# teensy_ms.net
KiCad netlist of a schematic drawn in EAGLE
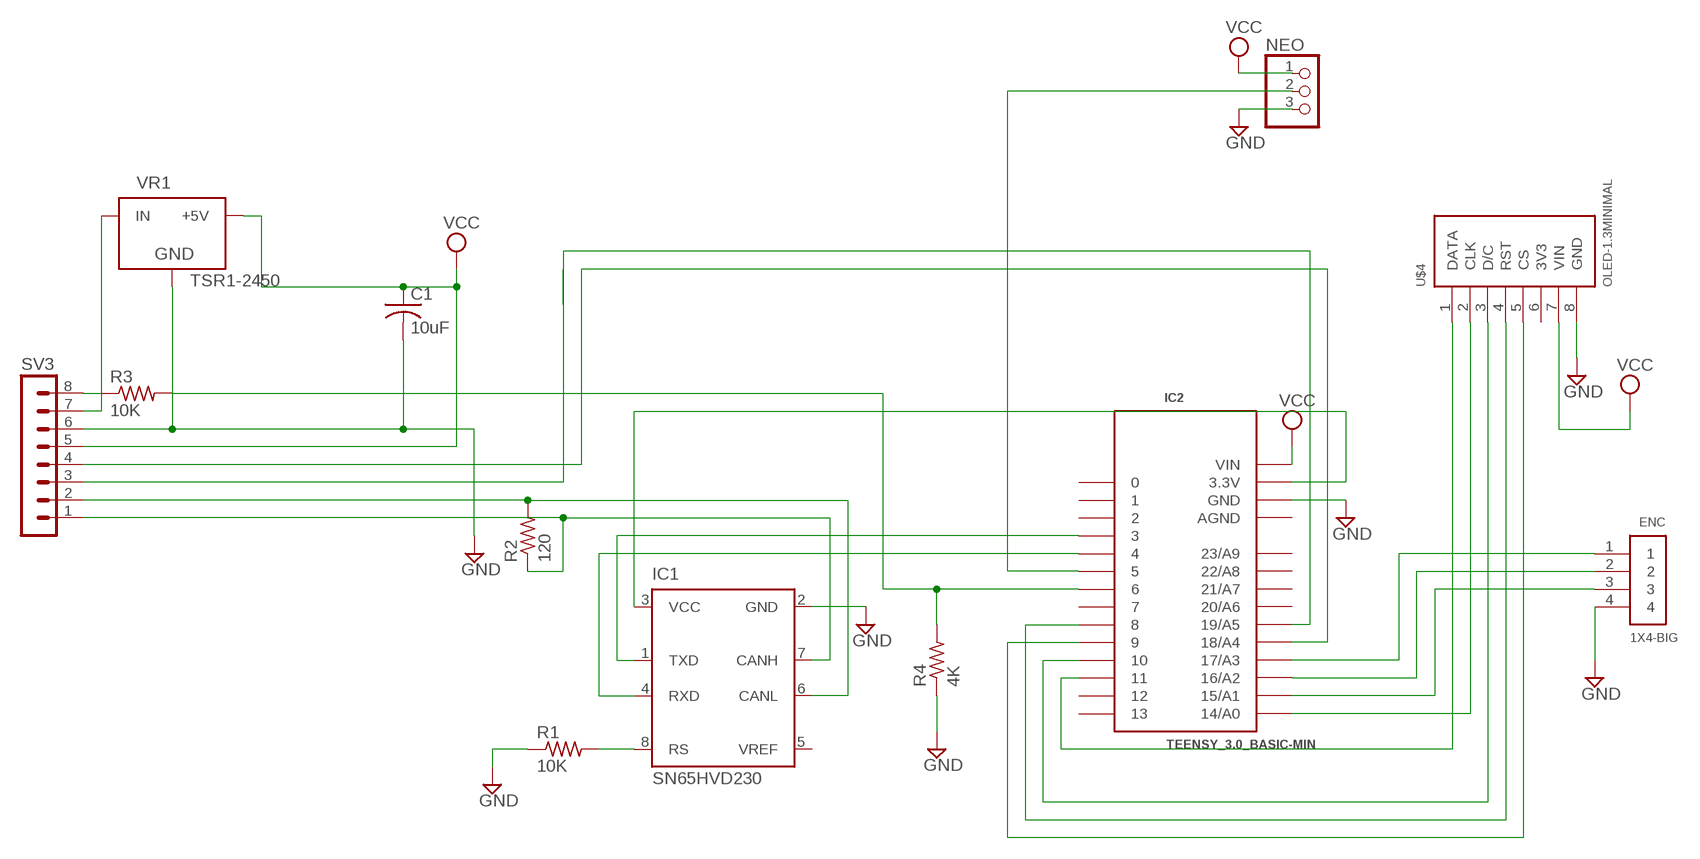
[diagram p0: schematic, sheet 1]

(export (version "E")
  (design (tool "Eeschema 10.0.6"))
  (components
    (comp (ref "C1")
      (value "10uF")
      (footprint "eagle-import:C1206")
      (libsource (lib "eagle-import") (part "C-USC1206"))
    )
    (comp (ref "ENC")
      (value "1X4-BIG")
      (footprint "eagle-import:1X04-BIG")
      (libsource (lib "eagle-import") (part "1X4-BIG"))
    )
    (comp (ref "IC1")
      (value "SN65HVD230")
      (footprint "eagle-import:SO8")
      (libsource (lib "eagle-import") (part "SN65HVD230"))
    )
    (comp (ref "IC2")
      (value "TEENSY_3.0_BASIC-MIN")
      (footprint "eagle-import:TEESNY_3.0_BASIC-MIN")
      (libsource (lib "eagle-import") (part "TEENSY_3.0_BASIC-MIN"))
    )
    (comp (ref "NEO")
      (value "PINHD-1X3")
      (footprint "eagle-import:1X03")
      (libsource (lib "eagle-import") (part "PINHD-1X3"))
    )
    (comp (ref "R1")
      (value "10K")
      (footprint "eagle-import:M1206")
      (libsource (lib "eagle-import") (part "R-US_M1206"))
    )
    (comp (ref "R2")
      (value "120")
      (footprint "eagle-import:M1206")
      (libsource (lib "eagle-import") (part "R-US_M1206"))
    )
    (comp (ref "R3")
      (value "10K")
      (footprint "eagle-import:M1206")
      (libsource (lib "eagle-import") (part "R-US_M1206"))
    )
    (comp (ref "R4")
      (value "4K")
      (footprint "eagle-import:M1206")
      (libsource (lib "eagle-import") (part "R-US_M1206"))
    )
    (comp (ref "SV3")
      (value "MA08-1")
      (footprint "eagle-import:MA08-1")
      (libsource (lib "eagle-import") (part "MA08-1"))
    )
    (comp (ref "U$4")
      (value "OLED-1.3MINIMAL")
      (footprint "eagle-import:OLED-1.3-BARE")
      (libsource (lib "eagle-import") (part "OLED-1.3MINIMAL"))
    )
    (comp (ref "VR1")
      (value "TSR1-2450")
      (footprint "eagle-import:TSR-1")
      (libsource (lib "eagle-import") (part "TSR1-2450"))
    )
  )
  (nets
    (net (code "1") (name "/AGND") (class "Default")
      (node (ref "IC2") (pin "AGND") (pinfunction "AGND_AGND") (pintype "power_in"))
    )
    (net (code "2") (name "GND") (class "Default")
      (node (ref "C1") (pin "2") (pinfunction "2_2") (pintype "passive"))
      (node (ref "ENC") (pin "4") (pinfunction "4_4") (pintype "bidirectional"))
      (node (ref "IC1") (pin "2") (pinfunction "GND_2") (pintype "power_in"))
      (node (ref "IC2") (pin "GND") (pinfunction "GND_GND") (pintype "power_in"))
      (node (ref "NEO") (pin "3") (pinfunction "3_3") (pintype "passive"))
      (node (ref "R1") (pin "1") (pinfunction "1_1") (pintype "passive"))
      (node (ref "R4") (pin "1") (pinfunction "1_1") (pintype "passive"))
      (node (ref "SV3") (pin "6") (pinfunction "6_6") (pintype "passive"))
      (node (ref "U$4") (pin "8") (pinfunction "GND_8") (pintype "bidirectional"))
      (node (ref "VR1") (pin "2") (pinfunction "GND_2") (pintype "power_in"))
    )
    (net (code "3") (name "Net-(ENC-Pad1)") (class "Default")
      (node (ref "ENC") (pin "1") (pinfunction "1_1") (pintype "bidirectional"))
      (node (ref "IC2") (pin "17/A3") (pinfunction "17/A3_17/A3") (pintype "bidirectional"))
    )
    (net (code "4") (name "Net-(ENC-Pad2)") (class "Default")
      (node (ref "ENC") (pin "2") (pinfunction "2_2") (pintype "bidirectional"))
      (node (ref "IC2") (pin "16/A2") (pinfunction "16/A2_16/A2") (pintype "bidirectional"))
    )
    (net (code "5") (name "Net-(ENC-Pad3)") (class "Default")
      (node (ref "ENC") (pin "3") (pinfunction "3_3") (pintype "bidirectional"))
      (node (ref "IC2") (pin "15/A1") (pinfunction "15/A1_15/A1") (pintype "bidirectional"))
    )
    (net (code "6") (name "Net-(IC1-CANH)") (class "Default")
      (node (ref "IC1") (pin "7") (pinfunction "CANH_7") (pintype "bidirectional"))
      (node (ref "R2") (pin "1") (pinfunction "1_1") (pintype "passive"))
      (node (ref "SV3") (pin "1") (pinfunction "1_1") (pintype "passive"))
    )
    (net (code "7") (name "Net-(IC1-CANL)") (class "Default")
      (node (ref "IC1") (pin "6") (pinfunction "CANL_6") (pintype "bidirectional"))
      (node (ref "R2") (pin "2") (pinfunction "2_2") (pintype "passive"))
      (node (ref "SV3") (pin "2") (pinfunction "2_2") (pintype "passive"))
    )
    (net (code "8") (name "Net-(IC1-RS)") (class "Default")
      (node (ref "IC1") (pin "8") (pinfunction "RS_8") (pintype "input"))
      (node (ref "R1") (pin "2") (pinfunction "2_2") (pintype "passive"))
    )
    (net (code "9") (name "Net-(IC1-RXD)") (class "Default")
      (node (ref "IC1") (pin "4") (pinfunction "RXD_4") (pintype "output"))
      (node (ref "IC2") (pin "4") (pinfunction "4_4") (pintype "bidirectional"))
    )
    (net (code "10") (name "Net-(IC1-TXD)") (class "Default")
      (node (ref "IC1") (pin "1") (pinfunction "TXD_1") (pintype "input"))
      (node (ref "IC2") (pin "3") (pinfunction "3_3") (pintype "bidirectional"))
    )
    (net (code "11") (name "Net-(IC1-VCC)") (class "Default")
      (node (ref "IC1") (pin "3") (pinfunction "VCC_3") (pintype "power_in"))
      (node (ref "IC2") (pin "3.3V") (pinfunction "3.3V_3.3V") (pintype "power_in"))
    )
    (net (code "12") (name "Net-(IC2-Pad5)") (class "Default")
      (node (ref "IC2") (pin "5") (pinfunction "5_5") (pintype "bidirectional"))
      (node (ref "NEO") (pin "2") (pinfunction "2_2") (pintype "passive"))
    )
    (net (code "13") (name "Net-(IC2-Pad6)") (class "Default")
      (node (ref "IC2") (pin "6") (pinfunction "6_6") (pintype "bidirectional"))
      (node (ref "R3") (pin "2") (pinfunction "2_2") (pintype "passive"))
      (node (ref "R4") (pin "2") (pinfunction "2_2") (pintype "passive"))
    )
    (net (code "14") (name "Net-(IC2-Pad18{slash}A4)") (class "Default")
      (node (ref "IC2") (pin "18/A4") (pinfunction "18/A4_18/A4") (pintype "bidirectional"))
      (node (ref "SV3") (pin "4") (pinfunction "4_4") (pintype "passive"))
    )
    (net (code "15") (name "Net-(IC2-Pad19{slash}A5)") (class "Default")
      (node (ref "IC2") (pin "19/A5") (pinfunction "19/A5_19/A5") (pintype "bidirectional"))
      (node (ref "SV3") (pin "3") (pinfunction "3_3") (pintype "passive"))
    )
    (net (code "16") (name "Net-(R3-Pad1)") (class "Default")
      (node (ref "R3") (pin "1") (pinfunction "1_1") (pintype "passive"))
      (node (ref "SV3") (pin "8") (pinfunction "8_8") (pintype "passive"))
    )
    (net (code "17") (name "Net-(U$4-CLK)") (class "Default")
      (node (ref "IC2") (pin "14/A0") (pinfunction "14/A0_14/A0") (pintype "bidirectional"))
      (node (ref "U$4") (pin "2") (pinfunction "CLK_2") (pintype "bidirectional"))
    )
    (net (code "18") (name "Net-(U$4-CS)") (class "Default")
      (node (ref "IC2") (pin "9") (pinfunction "9_9") (pintype "bidirectional"))
      (node (ref "U$4") (pin "5") (pinfunction "CS_5") (pintype "bidirectional"))
    )
    (net (code "19") (name "Net-(U$4-DATA)") (class "Default")
      (node (ref "IC2") (pin "11") (pinfunction "11_11") (pintype "bidirectional"))
      (node (ref "U$4") (pin "1") (pinfunction "DATA_1") (pintype "bidirectional"))
    )
    (net (code "20") (name "Net-(U$4-D{slash}C)") (class "Default")
      (node (ref "IC2") (pin "10") (pinfunction "10_10") (pintype "bidirectional"))
      (node (ref "U$4") (pin "3") (pinfunction "D/C_3") (pintype "bidirectional"))
    )
    (net (code "21") (name "Net-(U$4-RST)") (class "Default")
      (node (ref "IC2") (pin "8") (pinfunction "8_8") (pintype "bidirectional"))
      (node (ref "U$4") (pin "4") (pinfunction "RST_4") (pintype "bidirectional"))
    )
    (net (code "22") (name "Net-(VR1-IN)") (class "Default")
      (node (ref "SV3") (pin "7") (pinfunction "7_7") (pintype "passive"))
      (node (ref "VR1") (pin "1") (pinfunction "IN_1") (pintype "power_in"))
    )
    (net (code "23") (name "VCC") (class "Default")
      (node (ref "C1") (pin "1") (pinfunction "1_1") (pintype "passive"))
      (node (ref "IC2") (pin "VIN") (pinfunction "VIN_VIN") (pintype "power_in"))
      (node (ref "NEO") (pin "1") (pinfunction "1_1") (pintype "passive"))
      (node (ref "SV3") (pin "5") (pinfunction "5_5") (pintype "passive"))
      (node (ref "U$4") (pin "7") (pinfunction "VIN_7") (pintype "bidirectional"))
      (node (ref "VR1") (pin "3") (pinfunction "+5V_3") (pintype "power_in"))
    )
    (net (code "24") (name "unconnected-(IC1-VREF-Pad5)") (class "Default")
      (node (ref "IC1") (pin "5") (pinfunction "VREF_5") (pintype "output"))
    )
    (net (code "25") (name "unconnected-(IC2-Pad0)") (class "Default")
      (node (ref "IC2") (pin "0") (pinfunction "0_0") (pintype "bidirectional"))
    )
    (net (code "26") (name "unconnected-(IC2-Pad1)") (class "Default")
      (node (ref "IC2") (pin "1") (pinfunction "1_1") (pintype "bidirectional"))
    )
    (net (code "27") (name "unconnected-(IC2-Pad2)") (class "Default")
      (node (ref "IC2") (pin "2") (pinfunction "2_2") (pintype "bidirectional"))
    )
    (net (code "28") (name "unconnected-(IC2-Pad7)") (class "Default")
      (node (ref "IC2") (pin "7") (pinfunction "7_7") (pintype "bidirectional"))
    )
    (net (code "29") (name "unconnected-(IC2-Pad12)") (class "Default")
      (node (ref "IC2") (pin "12") (pinfunction "12_12") (pintype "bidirectional"))
    )
    (net (code "30") (name "unconnected-(IC2-Pad13)") (class "Default")
      (node (ref "IC2") (pin "13") (pinfunction "13_13") (pintype "bidirectional"))
    )
    (net (code "31") (name "unconnected-(IC2-Pad20{slash}A6)") (class "Default")
      (node (ref "IC2") (pin "20/A6") (pinfunction "20/A6_20/A6") (pintype "bidirectional"))
    )
    (net (code "32") (name "unconnected-(IC2-Pad21{slash}A7)") (class "Default")
      (node (ref "IC2") (pin "21/A7") (pinfunction "21/A7_21/A7") (pintype "bidirectional"))
    )
    (net (code "33") (name "unconnected-(IC2-Pad22{slash}A8)") (class "Default")
      (node (ref "IC2") (pin "22/A8") (pinfunction "22/A8_22/A8") (pintype "bidirectional"))
    )
    (net (code "34") (name "unconnected-(IC2-Pad23{slash}A9)") (class "Default")
      (node (ref "IC2") (pin "23/A9") (pinfunction "23/A9_23/A9") (pintype "bidirectional"))
    )
    (net (code "35") (name "unconnected-(U$4-3V3-Pad6)") (class "Default")
      (node (ref "U$4") (pin "6") (pinfunction "3V3_6") (pintype "bidirectional"))
    )
  )
)
